# BOTS_Latch.net
KiCad netlist of a schematic drawn in EAGLE
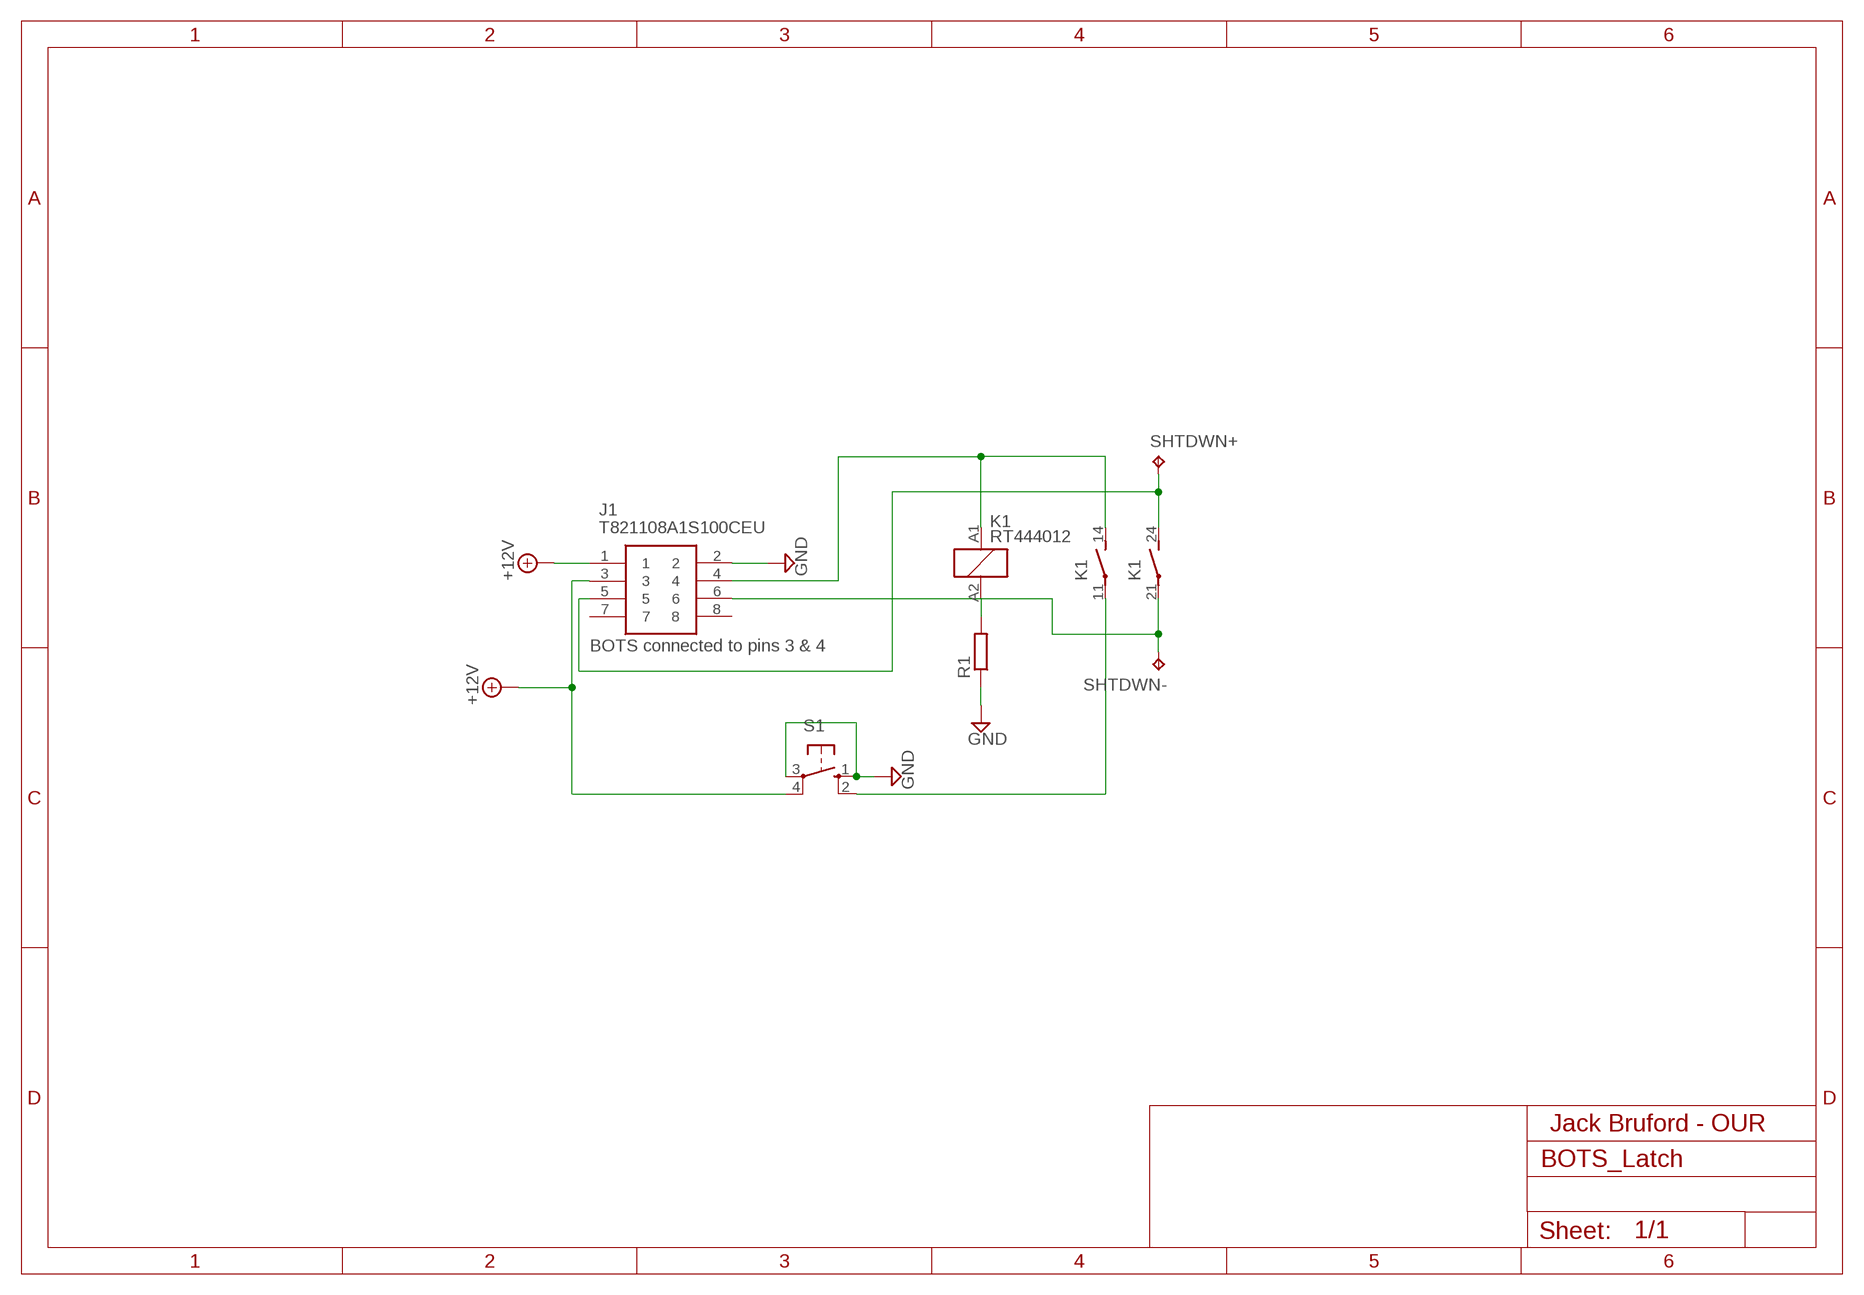
[diagram p0: schematic, sheet 1]

(export (version "E")
  (design (tool "Eeschema 10.0.6"))
  (components
    (comp (ref "J1")
      (value "T821108A1S100CEU")
      (footprint "eagle-import:HDRV8W64P254_2X4_1778X895X915P")
      (fields (field (name "RS_PART_NUMBER") "1702738"))
      (libsource (lib "eagle-import") (part "T821108A1S100CEU"))
    )
    (comp (ref "K1")
      (value "RT444012")
      (footprint "eagle-import:RT2N_O")
      (libsource (lib "eagle-import") (part "RT44?4012"))
    )
    (comp (ref "R1")
      (value "R-EU_0207/15")
      (footprint "eagle-import:0207_15")
      (libsource (lib "eagle-import") (part "R-EU_0207/15"))
    )
    (comp (ref "S1")
      (value "10-XX")
      (footprint "eagle-import:B3F-10XX")
      (fields (field (name "MPN") "B3F-1000"))
      (libsource (lib "eagle-import") (part "10-XX"))
    )
    (comp (ref "SHTDWN+")
      (value "TPPAD1-13")
      (footprint "eagle-import:P1-13")
      (libsource (lib "eagle-import") (part "TPPAD1-13"))
    )
    (comp (ref "SHTDWN-")
      (value "TPPAD1-13")
      (footprint "eagle-import:P1-13")
      (libsource (lib "eagle-import") (part "TPPAD1-13"))
    )
  )
  (nets
    (net (code "1") (name "+12V") (class "Default")
      (node (ref "J1") (pin "1") (pinfunction "1_1") (pintype "bidirectional"))
      (node (ref "J1") (pin "3") (pinfunction "3_3") (pintype "bidirectional"))
      (node (ref "S1") (pin "4") (pinfunction "P1_4") (pintype "passive"))
    )
    (net (code "2") (name "GND") (class "Default")
      (node (ref "J1") (pin "2") (pinfunction "2_2") (pintype "bidirectional"))
      (node (ref "R1") (pin "1") (pinfunction "1_1") (pintype "passive"))
      (node (ref "S1") (pin "1") (pinfunction "S_1") (pintype "passive"))
      (node (ref "S1") (pin "3") (pinfunction "P_3") (pintype "passive"))
    )
    (net (code "3") (name "Net-(K1A-1)") (class "Default")
      (node (ref "J1") (pin "4") (pinfunction "4_4") (pintype "bidirectional"))
      (node (ref "K1") (pin "14") (pinfunction "S_14") (pintype "passive"))
      (node (ref "K1") (pin "A1") (pinfunction "1_A1") (pintype "passive"))
    )
    (net (code "4") (name "Net-(K1A-2)") (class "Default")
      (node (ref "K1") (pin "A2") (pinfunction "2_A2") (pintype "passive"))
      (node (ref "R1") (pin "2") (pinfunction "2_2") (pintype "passive"))
    )
    (net (code "5") (name "Net-(K1B-P)") (class "Default")
      (node (ref "K1") (pin "11") (pinfunction "P_11") (pintype "passive"))
      (node (ref "S1") (pin "2") (pinfunction "S1_2") (pintype "passive"))
    )
    (net (code "6") (name "Net-(K1C-P)") (class "Default")
      (node (ref "J1") (pin "6") (pinfunction "6_6") (pintype "bidirectional"))
      (node (ref "K1") (pin "21") (pinfunction "P_21") (pintype "passive"))
      (node (ref "SHTDWN-") (pin "TP") (pinfunction "TP_TP") (pintype "input"))
    )
    (net (code "7") (name "Net-(K1C-S)") (class "Default")
      (node (ref "J1") (pin "5") (pinfunction "5_5") (pintype "bidirectional"))
      (node (ref "K1") (pin "24") (pinfunction "S_24") (pintype "passive"))
      (node (ref "SHTDWN+") (pin "TP") (pinfunction "TP_TP") (pintype "input"))
    )
    (net (code "8") (name "unconnected-(J1-Pad7)") (class "Default")
      (node (ref "J1") (pin "7") (pinfunction "7_7") (pintype "bidirectional"))
    )
    (net (code "9") (name "unconnected-(J1-Pad8)") (class "Default")
      (node (ref "J1") (pin "8") (pinfunction "8_8") (pintype "bidirectional"))
    )
  )
)
